# Hexagonal_MCU.net
KiCad netlist of a schematic drawn in EAGLE
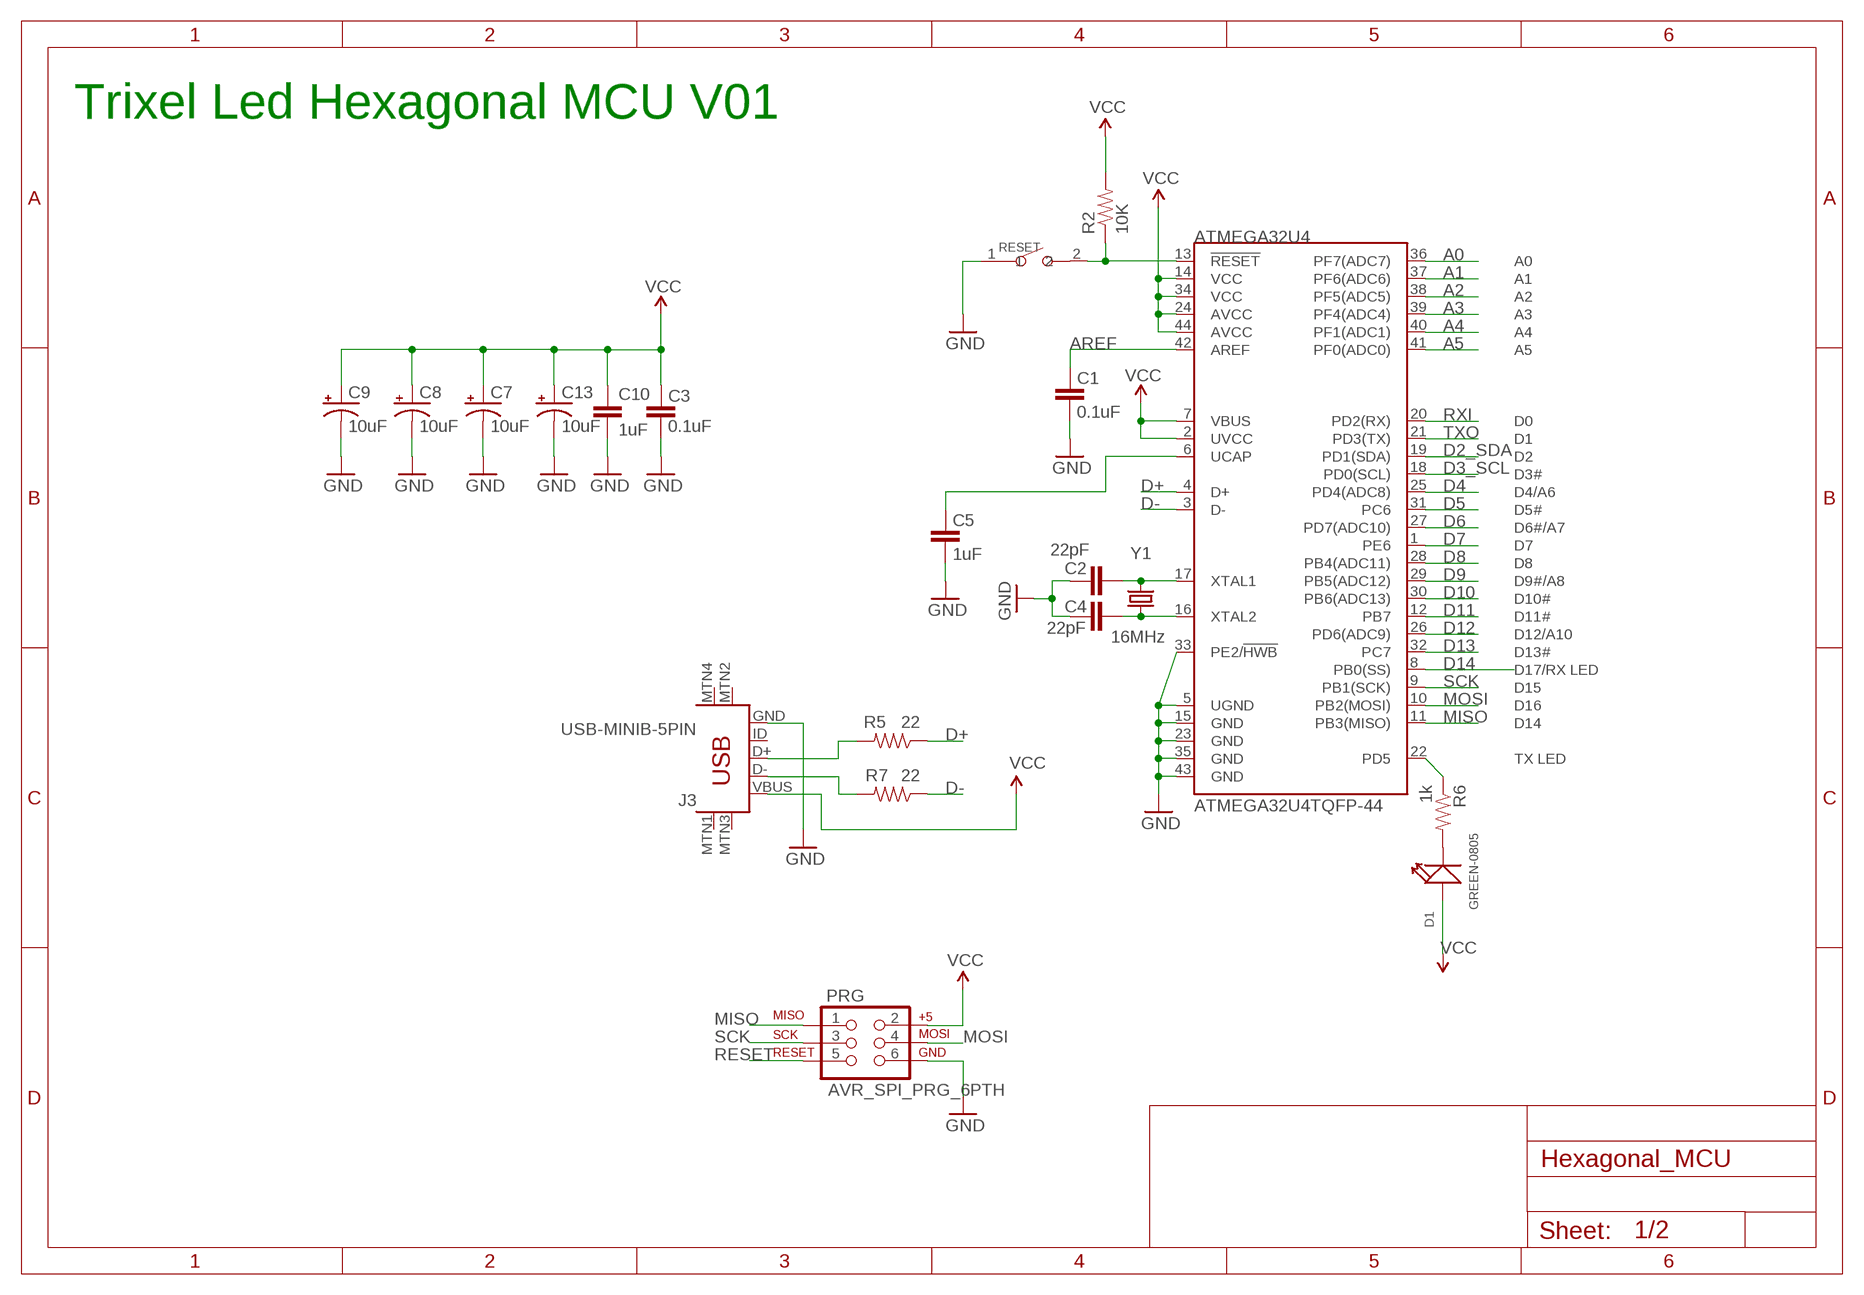
[diagram p0: schematic, sheet 1]
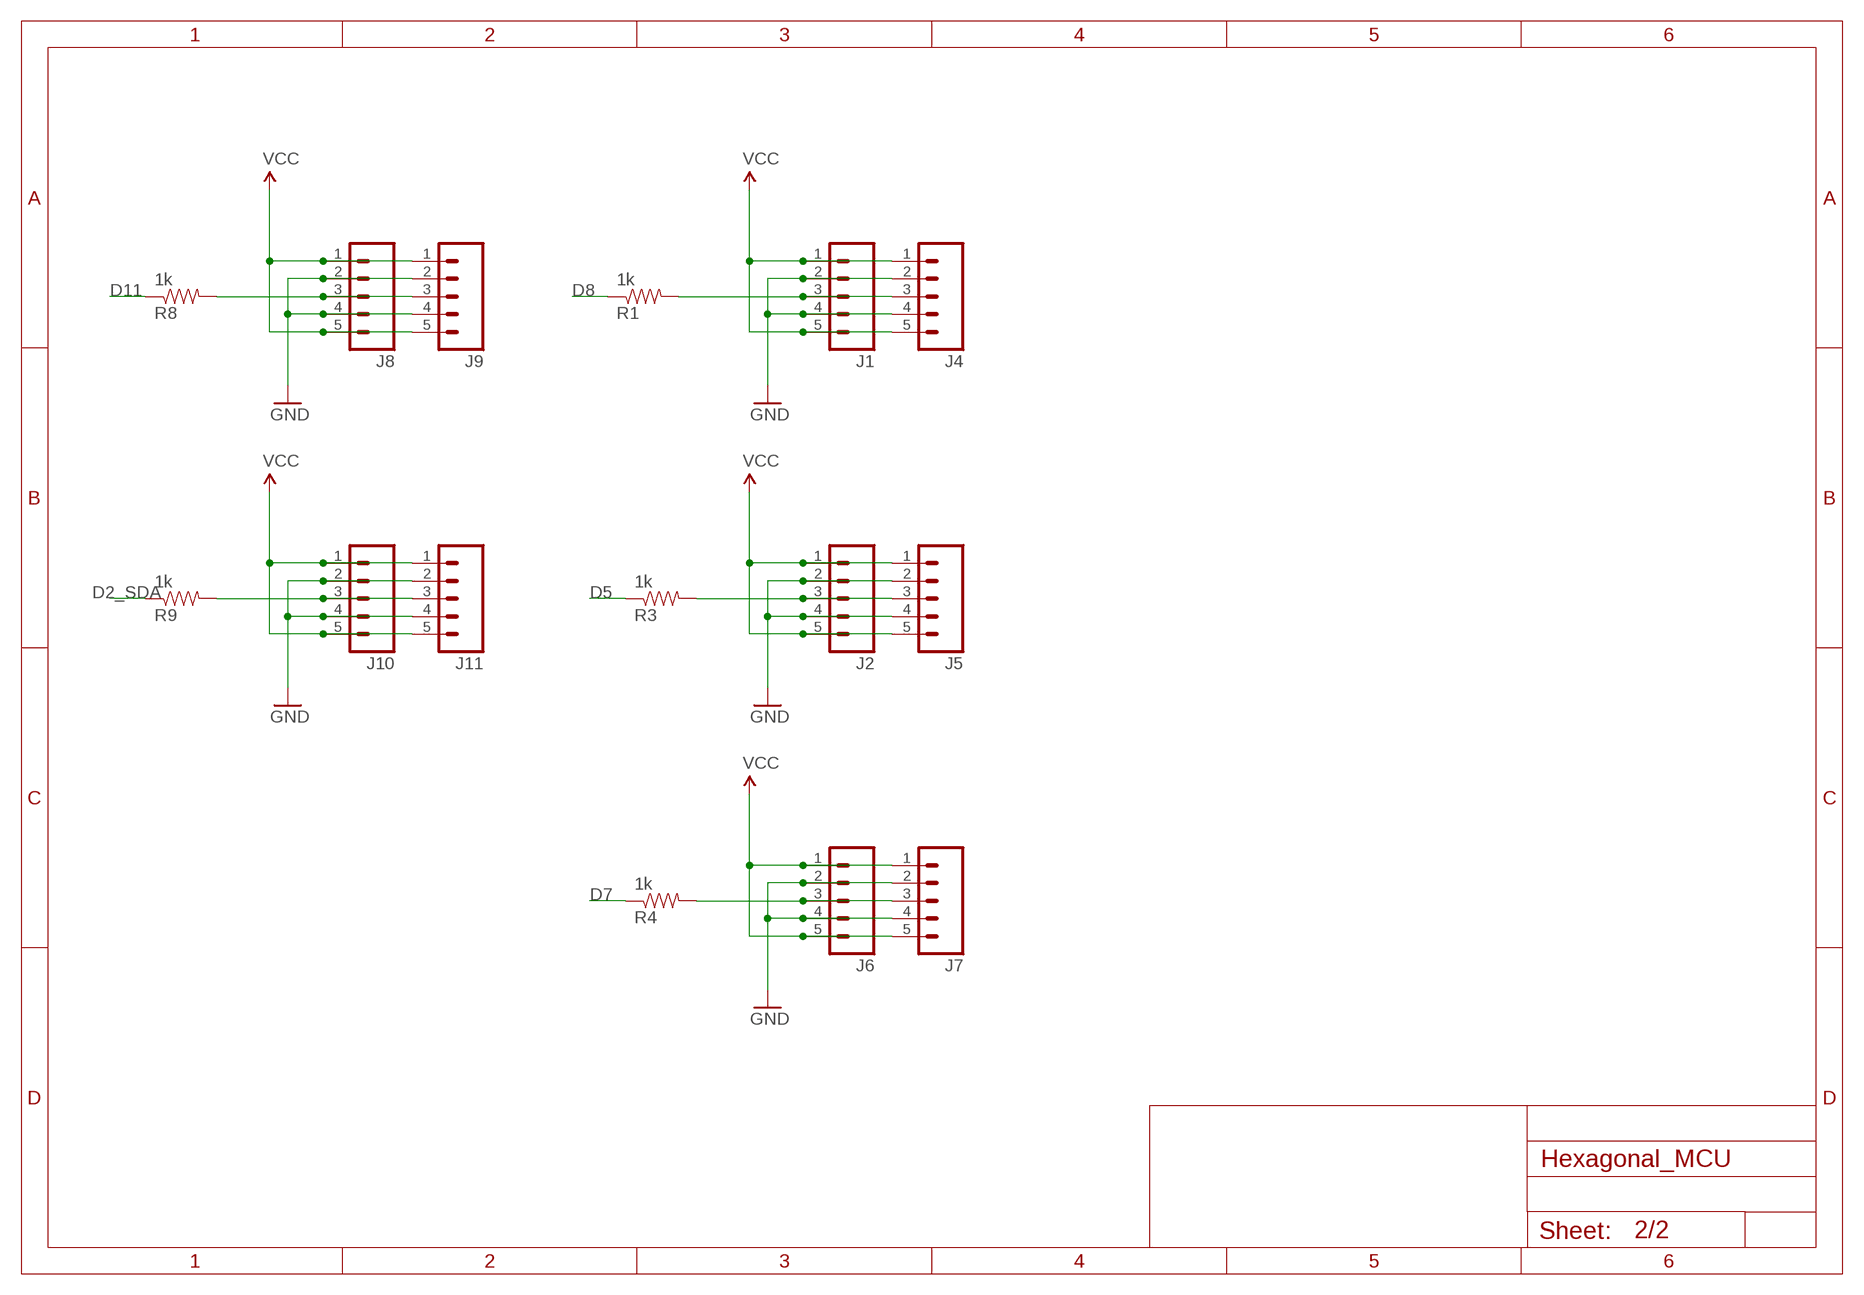
[diagram p1: schematic, sheet 2]

(export (version "E")
  (design (tool "Eeschema 10.0.6"))
  (components
    (comp (ref "J1")
      (value "M05NO_SILK")
      (footprint "eagle-import:1X05_NO_SILK")
      (libsource (lib "eagle-import") (part "M05NO_SILK"))
    )
    (comp (ref "J2")
      (value "M05NO_SILK")
      (footprint "eagle-import:1X05_NO_SILK")
      (libsource (lib "eagle-import") (part "M05NO_SILK"))
    )
    (comp (ref "J4")
      (value "M05PTH_LONGPADS")
      (footprint "eagle-import:1X05_LONGPADS")
      (libsource (lib "eagle-import") (part "M05PTH_LONGPADS"))
    )
    (comp (ref "J5")
      (value "M05PTH_LONGPADS")
      (footprint "eagle-import:1X05_LONGPADS")
      (libsource (lib "eagle-import") (part "M05PTH_LONGPADS"))
    )
    (comp (ref "J6")
      (value "M05NO_SILK")
      (footprint "eagle-import:1X05_NO_SILK")
      (libsource (lib "eagle-import") (part "M05NO_SILK"))
    )
    (comp (ref "J7")
      (value "M05PTH_LONGPADS")
      (footprint "eagle-import:1X05_LONGPADS")
      (libsource (lib "eagle-import") (part "M05PTH_LONGPADS"))
    )
    (comp (ref "J8")
      (value "M05NO_SILK")
      (footprint "eagle-import:1X05_NO_SILK")
      (libsource (lib "eagle-import") (part "M05NO_SILK"))
    )
    (comp (ref "J9")
      (value "M05PTH_LONGPADS")
      (footprint "eagle-import:1X05_LONGPADS")
      (libsource (lib "eagle-import") (part "M05PTH_LONGPADS"))
    )
    (comp (ref "J10")
      (value "M05NO_SILK")
      (footprint "eagle-import:1X05_NO_SILK")
      (libsource (lib "eagle-import") (part "M05NO_SILK"))
    )
    (comp (ref "J11")
      (value "M05PTH_LONGPADS")
      (footprint "eagle-import:1X05_LONGPADS")
      (libsource (lib "eagle-import") (part "M05PTH_LONGPADS"))
    )
    (comp (ref "R1")
      (value "1k")
      (footprint "eagle-import:0805")
      (libsource (lib "eagle-import") (part "RESISTOR0805-RES"))
    )
    (comp (ref "R3")
      (value "1k")
      (footprint "eagle-import:0805")
      (libsource (lib "eagle-import") (part "RESISTOR0805-RES"))
    )
    (comp (ref "R4")
      (value "1k")
      (footprint "eagle-import:0805")
      (libsource (lib "eagle-import") (part "RESISTOR0805-RES"))
    )
    (comp (ref "R8")
      (value "1k")
      (footprint "eagle-import:0805")
      (libsource (lib "eagle-import") (part "RESISTOR0805-RES"))
    )
    (comp (ref "R9")
      (value "1k")
      (footprint "eagle-import:0805")
      (libsource (lib "eagle-import") (part "RESISTOR0805-RES"))
    )
    (comp (ref "ATMEGA32U4")
      (value "ATMEGA32U4TQFP-44")
      (footprint "eagle-import:TQFP44")
      (libsource (lib "eagle-import") (part "ATMEGA32U4TQFP-44"))
    )
    (comp (ref "C1")
      (value "0.1uF")
      (footprint "eagle-import:0805")
      (libsource (lib "eagle-import") (part "CAP0805"))
    )
    (comp (ref "C2")
      (value "22pF")
      (footprint "eagle-import:0805")
      (libsource (lib "eagle-import") (part "CAP0805"))
    )
    (comp (ref "C3")
      (value "0.1uF")
      (footprint "eagle-import:0805")
      (libsource (lib "eagle-import") (part "CAP0805"))
    )
    (comp (ref "C4")
      (value "22pF")
      (footprint "eagle-import:0805")
      (libsource (lib "eagle-import") (part "CAP0805"))
    )
    (comp (ref "C5")
      (value "1uF")
      (footprint "eagle-import:0805")
      (libsource (lib "eagle-import") (part "CAP0805"))
    )
    (comp (ref "C7")
      (value "10uF")
      (footprint "eagle-import:EIA3216")
      (libsource (lib "eagle-import") (part "CAP_POL1206"))
    )
    (comp (ref "C8")
      (value "10uF")
      (footprint "eagle-import:EIA3216")
      (libsource (lib "eagle-import") (part "CAP_POL1206"))
    )
    (comp (ref "C9")
      (value "10uF")
      (footprint "eagle-import:EIA3216")
      (libsource (lib "eagle-import") (part "CAP_POL1206"))
    )
    (comp (ref "C10")
      (value "1uF")
      (footprint "eagle-import:0805")
      (libsource (lib "eagle-import") (part "CAP0805"))
    )
    (comp (ref "C13")
      (value "10uF")
      (footprint "eagle-import:EIA3216")
      (libsource (lib "eagle-import") (part "CAP_POL1206"))
    )
    (comp (ref "D1")
      (value "GREEN-0805")
      (footprint "eagle-import:LED-0805")
      (fields (field (name "MPN") "17-215SYGC/S530-E2/TR8"))
      (libsource (lib "eagle-import") (part "SMD-LED-CLEAR-GREEN(0805)"))
    )
    (comp (ref "J3")
      (value "USB-MINIB-5PIN")
      (footprint "eagle-import:USB-MINIB")
      (libsource (lib "eagle-import") (part "USB-MINIB-5PIN"))
    )
    (comp (ref "PRG")
      (value "AVR_SPI_PRG_6PTH")
      (footprint "eagle-import:2X3")
      (libsource (lib "eagle-import") (part "AVR_SPI_PRG_6PTH"))
    )
    (comp (ref "R2")
      (value "10K")
      (footprint "eagle-import:0805")
      (libsource (lib "eagle-import") (part "RESISTOR0805-RES"))
    )
    (comp (ref "R5")
      (value "22")
      (footprint "eagle-import:0805")
      (libsource (lib "eagle-import") (part "RESISTOR0805-RES"))
    )
    (comp (ref "R6")
      (value "1k")
      (footprint "eagle-import:0805")
      (libsource (lib "eagle-import") (part "RESISTOR0805-RES"))
    )
    (comp (ref "R7")
      (value "22")
      (footprint "eagle-import:0805")
      (libsource (lib "eagle-import") (part "RESISTOR0805-RES"))
    )
    (comp (ref "RESET")
      (value "B3U-1000P-2P-SMD")
      (footprint "eagle-import:SW2-4.0X3.0X2.0")
      (libsource (lib "eagle-import") (part "SMD-BUTTON(2P-4.0X3.0X1.5+0.5MM)SW-TS-017A-2P"))
    )
    (comp (ref "Y1")
      (value "16MHz")
      (footprint "eagle-import:HC49US")
      (libsource (lib "eagle-import") (part "CRYSTALHC49US"))
    )
  )
  (nets
    (net (code "1") (name "5V") (class "Default")
      (node (ref "ATMEGA32U4") (pin "14") (pinfunction "VCC_14") (pintype "bidirectional"))
      (node (ref "ATMEGA32U4") (pin "2") (pinfunction "UVCC_2") (pintype "bidirectional"))
      (node (ref "ATMEGA32U4") (pin "24") (pinfunction "AVCC_24") (pintype "bidirectional"))
      (node (ref "ATMEGA32U4") (pin "34") (pinfunction "VCC_34") (pintype "bidirectional"))
      (node (ref "ATMEGA32U4") (pin "44") (pinfunction "AVCC_44") (pintype "bidirectional"))
      (node (ref "ATMEGA32U4") (pin "7") (pinfunction "VBUS_7") (pintype "bidirectional"))
      (node (ref "C10") (pin "1") (pinfunction "1_1") (pintype "passive"))
      (node (ref "C13") (pin "A") (pinfunction "+_A") (pintype "passive"))
      (node (ref "C3") (pin "2") (pinfunction "2_2") (pintype "passive"))
      (node (ref "C7") (pin "A") (pinfunction "+_A") (pintype "passive"))
      (node (ref "C8") (pin "A") (pinfunction "+_A") (pintype "passive"))
      (node (ref "C9") (pin "A") (pinfunction "+_A") (pintype "passive"))
      (node (ref "D1") (pin "+") (pinfunction "+_+") (pintype "passive"))
      (node (ref "J1") (pin "1") (pinfunction "1_1") (pintype "passive"))
      (node (ref "J1") (pin "5") (pinfunction "5_5") (pintype "passive"))
      (node (ref "J10") (pin "1") (pinfunction "1_1") (pintype "passive"))
      (node (ref "J10") (pin "5") (pinfunction "5_5") (pintype "passive"))
      (node (ref "J11") (pin "1") (pinfunction "1_1") (pintype "passive"))
      (node (ref "J11") (pin "5") (pinfunction "5_5") (pintype "passive"))
      (node (ref "J2") (pin "1") (pinfunction "1_1") (pintype "passive"))
      (node (ref "J2") (pin "5") (pinfunction "5_5") (pintype "passive"))
      (node (ref "J3") (pin "VBUS") (pinfunction "VBUS_VBUS") (pintype "bidirectional"))
      (node (ref "J4") (pin "1") (pinfunction "1_1") (pintype "passive"))
      (node (ref "J4") (pin "5") (pinfunction "5_5") (pintype "passive"))
      (node (ref "J5") (pin "1") (pinfunction "1_1") (pintype "passive"))
      (node (ref "J5") (pin "5") (pinfunction "5_5") (pintype "passive"))
      (node (ref "J6") (pin "1") (pinfunction "1_1") (pintype "passive"))
      (node (ref "J6") (pin "5") (pinfunction "5_5") (pintype "passive"))
      (node (ref "J7") (pin "1") (pinfunction "1_1") (pintype "passive"))
      (node (ref "J7") (pin "5") (pinfunction "5_5") (pintype "passive"))
      (node (ref "J8") (pin "1") (pinfunction "1_1") (pintype "passive"))
      (node (ref "J8") (pin "5") (pinfunction "5_5") (pintype "passive"))
      (node (ref "J9") (pin "1") (pinfunction "1_1") (pintype "passive"))
      (node (ref "J9") (pin "5") (pinfunction "5_5") (pintype "passive"))
      (node (ref "PRG") (pin "2") (pinfunction "2_2") (pintype "passive"))
      (node (ref "R2") (pin "2") (pinfunction "2_2") (pintype "passive"))
    )
    (net (code "2") (name "A0") (class "Default")
      (node (ref "ATMEGA32U4") (pin "36") (pinfunction "PF7(ADC7)_36") (pintype "bidirectional"))
    )
    (net (code "3") (name "A1") (class "Default")
      (node (ref "ATMEGA32U4") (pin "37") (pinfunction "PF6(ADC6)_37") (pintype "bidirectional"))
    )
    (net (code "4") (name "A2") (class "Default")
      (node (ref "ATMEGA32U4") (pin "38") (pinfunction "PF5(ADC5)_38") (pintype "bidirectional"))
    )
    (net (code "5") (name "A3") (class "Default")
      (node (ref "ATMEGA32U4") (pin "39") (pinfunction "PF4(ADC4)_39") (pintype "bidirectional"))
    )
    (net (code "6") (name "A4") (class "Default")
      (node (ref "ATMEGA32U4") (pin "40") (pinfunction "PF1(ADC1)_40") (pintype "bidirectional"))
    )
    (net (code "7") (name "A5") (class "Default")
      (node (ref "ATMEGA32U4") (pin "41") (pinfunction "PF0(ADC0)_41") (pintype "bidirectional"))
    )
    (net (code "8") (name "AREF") (class "Default")
      (node (ref "ATMEGA32U4") (pin "42") (pinfunction "AREF_42") (pintype "bidirectional"))
      (node (ref "C1") (pin "2") (pinfunction "2_2") (pintype "passive"))
    )
    (net (code "9") (name "D+") (class "Default")
      (node (ref "ATMEGA32U4") (pin "4") (pinfunction "D+_4") (pintype "bidirectional"))
      (node (ref "R5") (pin "1") (pinfunction "1_1") (pintype "passive"))
    )
    (net (code "10") (name "D-") (class "Default")
      (node (ref "ATMEGA32U4") (pin "3") (pinfunction "D-_3") (pintype "bidirectional"))
      (node (ref "R7") (pin "1") (pinfunction "1_1") (pintype "passive"))
    )
    (net (code "11") (name "D2_SDA") (class "Default")
      (node (ref "ATMEGA32U4") (pin "19") (pinfunction "PD1(SDA)_19") (pintype "bidirectional"))
      (node (ref "R9") (pin "1") (pinfunction "1_1") (pintype "passive"))
    )
    (net (code "12") (name "D3_SCL") (class "Default")
      (node (ref "ATMEGA32U4") (pin "18") (pinfunction "PD0(SCL)_18") (pintype "bidirectional"))
    )
    (net (code "13") (name "D4") (class "Default")
      (node (ref "ATMEGA32U4") (pin "25") (pinfunction "PD4(ADC8)_25") (pintype "bidirectional"))
    )
    (net (code "14") (name "D5") (class "Default")
      (node (ref "ATMEGA32U4") (pin "31") (pinfunction "PC6_31") (pintype "bidirectional"))
      (node (ref "R3") (pin "1") (pinfunction "1_1") (pintype "passive"))
    )
    (net (code "15") (name "D6") (class "Default")
      (node (ref "ATMEGA32U4") (pin "27") (pinfunction "PD7(ADC10)_27") (pintype "bidirectional"))
    )
    (net (code "16") (name "D7") (class "Default")
      (node (ref "ATMEGA32U4") (pin "1") (pinfunction "PE6_1") (pintype "bidirectional"))
      (node (ref "R4") (pin "1") (pinfunction "1_1") (pintype "passive"))
    )
    (net (code "17") (name "D8") (class "Default")
      (node (ref "ATMEGA32U4") (pin "28") (pinfunction "PB4(ADC11)_28") (pintype "bidirectional"))
      (node (ref "R1") (pin "1") (pinfunction "1_1") (pintype "passive"))
    )
    (net (code "18") (name "D9") (class "Default")
      (node (ref "ATMEGA32U4") (pin "29") (pinfunction "PB5(ADC12)_29") (pintype "bidirectional"))
    )
    (net (code "19") (name "D10") (class "Default")
      (node (ref "ATMEGA32U4") (pin "30") (pinfunction "PB6(ADC13)_30") (pintype "bidirectional"))
    )
    (net (code "20") (name "D11") (class "Default")
      (node (ref "ATMEGA32U4") (pin "12") (pinfunction "PB7_12") (pintype "bidirectional"))
      (node (ref "R8") (pin "1") (pinfunction "1_1") (pintype "passive"))
    )
    (net (code "21") (name "D12") (class "Default")
      (node (ref "ATMEGA32U4") (pin "26") (pinfunction "PD6(ADC9)_26") (pintype "bidirectional"))
    )
    (net (code "22") (name "D13") (class "Default")
      (node (ref "ATMEGA32U4") (pin "32") (pinfunction "PC7_32") (pintype "bidirectional"))
    )
    (net (code "23") (name "D14") (class "Default")
      (node (ref "ATMEGA32U4") (pin "8") (pinfunction "PB0(SS)_8") (pintype "bidirectional"))
    )
    (net (code "24") (name "GND") (class "Default")
      (node (ref "ATMEGA32U4") (pin "15") (pinfunction "GND_15") (pintype "bidirectional"))
      (node (ref "ATMEGA32U4") (pin "23") (pinfunction "GND_23") (pintype "bidirectional"))
      (node (ref "ATMEGA32U4") (pin "33") (pinfunction "PE2/~{HWB}_33") (pintype "bidirectional"))
      (node (ref "ATMEGA32U4") (pin "35") (pinfunction "GND_35") (pintype "bidirectional"))
      (node (ref "ATMEGA32U4") (pin "43") (pinfunction "GND_43") (pintype "bidirectional"))
      (node (ref "ATMEGA32U4") (pin "5") (pinfunction "UGND_5") (pintype "bidirectional"))
      (node (ref "C1") (pin "1") (pinfunction "1_1") (pintype "passive"))
      (node (ref "C10") (pin "2") (pinfunction "2_2") (pintype "passive"))
      (node (ref "C13") (pin "C") (pinfunction "-_C") (pintype "passive"))
      (node (ref "C2") (pin "2") (pinfunction "2_2") (pintype "passive"))
      (node (ref "C3") (pin "1") (pinfunction "1_1") (pintype "passive"))
      (node (ref "C4") (pin "2") (pinfunction "2_2") (pintype "passive"))
      (node (ref "C5") (pin "1") (pinfunction "1_1") (pintype "passive"))
      (node (ref "C7") (pin "C") (pinfunction "-_C") (pintype "passive"))
      (node (ref "C8") (pin "C") (pinfunction "-_C") (pintype "passive"))
      (node (ref "C9") (pin "C") (pinfunction "-_C") (pintype "passive"))
      (node (ref "J1") (pin "2") (pinfunction "2_2") (pintype "passive"))
      (node (ref "J1") (pin "4") (pinfunction "4_4") (pintype "passive"))
      (node (ref "J10") (pin "2") (pinfunction "2_2") (pintype "passive"))
      (node (ref "J10") (pin "4") (pinfunction "4_4") (pintype "passive"))
      (node (ref "J11") (pin "2") (pinfunction "2_2") (pintype "passive"))
      (node (ref "J11") (pin "4") (pinfunction "4_4") (pintype "passive"))
      (node (ref "J2") (pin "2") (pinfunction "2_2") (pintype "passive"))
      (node (ref "J2") (pin "4") (pinfunction "4_4") (pintype "passive"))
      (node (ref "J3") (pin "GND") (pinfunction "GND_GND") (pintype "bidirectional"))
      (node (ref "J4") (pin "2") (pinfunction "2_2") (pintype "passive"))
      (node (ref "J4") (pin "4") (pinfunction "4_4") (pintype "passive"))
      (node (ref "J5") (pin "2") (pinfunction "2_2") (pintype "passive"))
      (node (ref "J5") (pin "4") (pinfunction "4_4") (pintype "passive"))
      (node (ref "J6") (pin "2") (pinfunction "2_2") (pintype "passive"))
      (node (ref "J6") (pin "4") (pinfunction "4_4") (pintype "passive"))
      (node (ref "J7") (pin "2") (pinfunction "2_2") (pintype "passive"))
      (node (ref "J7") (pin "4") (pinfunction "4_4") (pintype "passive"))
      (node (ref "J8") (pin "2") (pinfunction "2_2") (pintype "passive"))
      (node (ref "J8") (pin "4") (pinfunction "4_4") (pintype "passive"))
      (node (ref "J9") (pin "2") (pinfunction "2_2") (pintype "passive"))
      (node (ref "J9") (pin "4") (pinfunction "4_4") (pintype "passive"))
      (node (ref "PRG") (pin "6") (pinfunction "6_6") (pintype "passive"))
      (node (ref "RESET") (pin "1") (pinfunction "1_1") (pintype "bidirectional"))
    )
    (net (code "25") (name "MISO") (class "Default")
      (node (ref "ATMEGA32U4") (pin "11") (pinfunction "PB3(MISO)_11") (pintype "bidirectional"))
      (node (ref "PRG") (pin "1") (pinfunction "1_1") (pintype "passive"))
    )
    (net (code "26") (name "MOSI") (class "Default")
      (node (ref "ATMEGA32U4") (pin "10") (pinfunction "PB2(MOSI)_10") (pintype "bidirectional"))
      (node (ref "PRG") (pin "4") (pinfunction "4_4") (pintype "passive"))
    )
    (net (code "27") (name "Net-(ATMEGA32U4-PD5)") (class "Default")
      (node (ref "ATMEGA32U4") (pin "22") (pinfunction "PD5_22") (pintype "bidirectional"))
      (node (ref "R6") (pin "1") (pinfunction "1_1") (pintype "passive"))
    )
    (net (code "28") (name "Net-(ATMEGA32U4-UCAP)") (class "Default")
      (node (ref "ATMEGA32U4") (pin "6") (pinfunction "UCAP_6") (pintype "bidirectional"))
      (node (ref "C5") (pin "2") (pinfunction "2_2") (pintype "passive"))
    )
    (net (code "29") (name "Net-(ATMEGA32U4-XTAL1)") (class "Default")
      (node (ref "ATMEGA32U4") (pin "17") (pinfunction "XTAL1_17") (pintype "bidirectional"))
      (node (ref "C2") (pin "1") (pinfunction "1_1") (pintype "passive"))
      (node (ref "Y1") (pin "2") (pinfunction "2_2") (pintype "passive"))
    )
    (net (code "30") (name "Net-(ATMEGA32U4-XTAL2)") (class "Default")
      (node (ref "ATMEGA32U4") (pin "16") (pinfunction "XTAL2_16") (pintype "bidirectional"))
      (node (ref "C4") (pin "1") (pinfunction "1_1") (pintype "passive"))
      (node (ref "Y1") (pin "1") (pinfunction "1_1") (pintype "passive"))
    )
    (net (code "31") (name "Net-(D1-Pad-)") (class "Default")
      (node (ref "D1") (pin "-") (pinfunction "-_-") (pintype "passive"))
      (node (ref "R6") (pin "2") (pinfunction "2_2") (pintype "passive"))
    )
    (net (code "32") (name "Net-(J1-Pad3)") (class "Default")
      (node (ref "J1") (pin "3") (pinfunction "3_3") (pintype "passive"))
      (node (ref "J4") (pin "3") (pinfunction "3_3") (pintype "passive"))
      (node (ref "R1") (pin "2") (pinfunction "2_2") (pintype "passive"))
    )
    (net (code "33") (name "Net-(J2-Pad3)") (class "Default")
      (node (ref "J2") (pin "3") (pinfunction "3_3") (pintype "passive"))
      (node (ref "J5") (pin "3") (pinfunction "3_3") (pintype "passive"))
      (node (ref "R3") (pin "2") (pinfunction "2_2") (pintype "passive"))
    )
    (net (code "34") (name "Net-(J3-PadD+)") (class "Default")
      (node (ref "J3") (pin "D+") (pinfunction "D+_D+") (pintype "bidirectional"))
      (node (ref "R5") (pin "2") (pinfunction "2_2") (pintype "passive"))
    )
    (net (code "35") (name "Net-(J3-PadD-)") (class "Default")
      (node (ref "J3") (pin "D-") (pinfunction "D-_D-") (pintype "bidirectional"))
      (node (ref "R7") (pin "2") (pinfunction "2_2") (pintype "passive"))
    )
    (net (code "36") (name "Net-(J6-Pad3)") (class "Default")
      (node (ref "J6") (pin "3") (pinfunction "3_3") (pintype "passive"))
      (node (ref "J7") (pin "3") (pinfunction "3_3") (pintype "passive"))
      (node (ref "R4") (pin "2") (pinfunction "2_2") (pintype "passive"))
    )
    (net (code "37") (name "Net-(J8-Pad3)") (class "Default")
      (node (ref "J8") (pin "3") (pinfunction "3_3") (pintype "passive"))
      (node (ref "J9") (pin "3") (pinfunction "3_3") (pintype "passive"))
      (node (ref "R8") (pin "2") (pinfunction "2_2") (pintype "passive"))
    )
    (net (code "38") (name "Net-(J10-Pad3)") (class "Default")
      (node (ref "J10") (pin "3") (pinfunction "3_3") (pintype "passive"))
      (node (ref "J11") (pin "3") (pinfunction "3_3") (pintype "passive"))
      (node (ref "R9") (pin "2") (pinfunction "2_2") (pintype "passive"))
    )
    (net (code "39") (name "RESET") (class "Default")
      (node (ref "ATMEGA32U4") (pin "13") (pinfunction "~{RESET}_13") (pintype "bidirectional"))
      (node (ref "PRG") (pin "5") (pinfunction "5_5") (pintype "passive"))
      (node (ref "R2") (pin "1") (pinfunction "1_1") (pintype "passive"))
      (node (ref "RESET") (pin "2") (pinfunction "2_2") (pintype "bidirectional"))
    )
    (net (code "40") (name "RXI") (class "Default")
      (node (ref "ATMEGA32U4") (pin "20") (pinfunction "PD2(RX)_20") (pintype "bidirectional"))
    )
    (net (code "41") (name "SCK") (class "Default")
      (node (ref "ATMEGA32U4") (pin "9") (pinfunction "PB1(SCK)_9") (pintype "bidirectional"))
      (node (ref "PRG") (pin "3") (pinfunction "3_3") (pintype "passive"))
    )
    (net (code "42") (name "TXO") (class "Default")
      (node (ref "ATMEGA32U4") (pin "21") (pinfunction "PD3(TX)_21") (pintype "bidirectional"))
    )
    (net (code "43") (name "unconnected-(J3-MTN1-PadMTN3)") (class "Default")
      (node (ref "J3") (pin "MTN3") (pinfunction "MTN1_MTN3") (pintype "bidirectional"))
    )
    (net (code "44") (name "unconnected-(J3-MTN2-PadMTN1)") (class "Default")
      (node (ref "J3") (pin "MTN1") (pinfunction "MTN2_MTN1") (pintype "bidirectional"))
    )
    (net (code "45") (name "unconnected-(J3-MTN3-PadMTN2)") (class "Default")
      (node (ref "J3") (pin "MTN2") (pinfunction "MTN3_MTN2") (pintype "bidirectional"))
    )
    (net (code "46") (name "unconnected-(J3-PadID)") (class "Default")
      (node (ref "J3") (pin "ID") (pinfunction "ID_ID") (pintype "bidirectional"))
    )
    (net (code "47") (name "unconnected-(J3-PadMTN4)") (class "Default")
      (node (ref "J3") (pin "MTN4") (pinfunction "MTN4_MTN4") (pintype "bidirectional"))
    )
  )
)
